# LEDMatrix.net
KiCad netlist of a schematic drawn in EAGLE
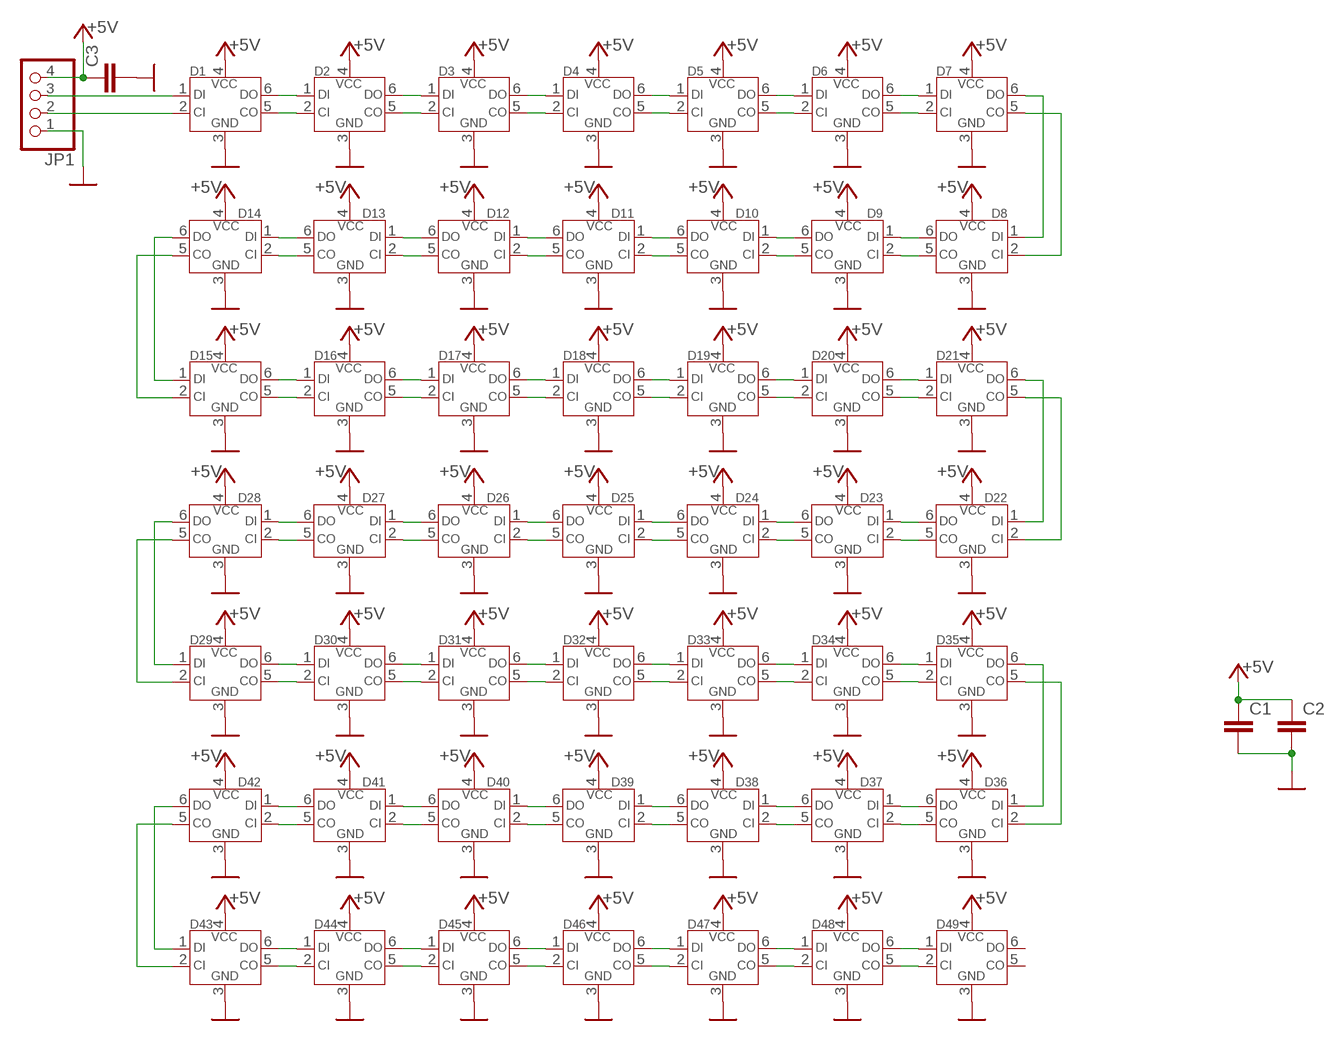
[diagram p0: schematic, sheet 1]

(export (version "E")
  (design (tool "Eeschema 10.0.6"))
  (components
    (comp (ref "C1")
      (value "C-EUC0805")
      (footprint "eagle-import:C0805")
      (libsource (lib "eagle-import") (part "C-EUC0805"))
    )
    (comp (ref "C2")
      (value "C-EUC0805")
      (footprint "eagle-import:C0805")
      (libsource (lib "eagle-import") (part "C-EUC0805"))
    )
    (comp (ref "C3")
      (value "C-EUC0805")
      (footprint "eagle-import:C0805")
      (libsource (lib "eagle-import") (part "C-EUC0805"))
    )
    (comp (ref "D1")
      (value "QBLP679E-RGB")
      (footprint "eagle-import:LED_QBLP679E-RGB")
      (fields (field (name "MF") "QT Brightek"))
      (libsource (lib "eagle-import") (part "QBLP679E-RGB"))
    )
    (comp (ref "D2")
      (value "QBLP679E-RGB")
      (footprint "eagle-import:LED_QBLP679E-RGB")
      (fields (field (name "MF") "QT Brightek"))
      (libsource (lib "eagle-import") (part "QBLP679E-RGB"))
    )
    (comp (ref "D3")
      (value "QBLP679E-RGB")
      (footprint "eagle-import:LED_QBLP679E-RGB")
      (fields (field (name "MF") "QT Brightek"))
      (libsource (lib "eagle-import") (part "QBLP679E-RGB"))
    )
    (comp (ref "D4")
      (value "QBLP679E-RGB")
      (footprint "eagle-import:LED_QBLP679E-RGB")
      (fields (field (name "MF") "QT Brightek"))
      (libsource (lib "eagle-import") (part "QBLP679E-RGB"))
    )
    (comp (ref "D5")
      (value "QBLP679E-RGB")
      (footprint "eagle-import:LED_QBLP679E-RGB")
      (fields (field (name "MF") "QT Brightek"))
      (libsource (lib "eagle-import") (part "QBLP679E-RGB"))
    )
    (comp (ref "D6")
      (value "QBLP679E-RGB")
      (footprint "eagle-import:LED_QBLP679E-RGB")
      (fields (field (name "MF") "QT Brightek"))
      (libsource (lib "eagle-import") (part "QBLP679E-RGB"))
    )
    (comp (ref "D7")
      (value "QBLP679E-RGB")
      (footprint "eagle-import:LED_QBLP679E-RGB")
      (fields (field (name "MF") "QT Brightek"))
      (libsource (lib "eagle-import") (part "QBLP679E-RGB"))
    )
    (comp (ref "D8")
      (value "QBLP679E-RGB")
      (footprint "eagle-import:LED_QBLP679E-RGB")
      (fields (field (name "MF") "QT Brightek"))
      (libsource (lib "eagle-import") (part "QBLP679E-RGB"))
    )
    (comp (ref "D9")
      (value "QBLP679E-RGB")
      (footprint "eagle-import:LED_QBLP679E-RGB")
      (fields (field (name "MF") "QT Brightek"))
      (libsource (lib "eagle-import") (part "QBLP679E-RGB"))
    )
    (comp (ref "D10")
      (value "QBLP679E-RGB")
      (footprint "eagle-import:LED_QBLP679E-RGB")
      (fields (field (name "MF") "QT Brightek"))
      (libsource (lib "eagle-import") (part "QBLP679E-RGB"))
    )
    (comp (ref "D11")
      (value "QBLP679E-RGB")
      (footprint "eagle-import:LED_QBLP679E-RGB")
      (fields (field (name "MF") "QT Brightek"))
      (libsource (lib "eagle-import") (part "QBLP679E-RGB"))
    )
    (comp (ref "D12")
      (value "QBLP679E-RGB")
      (footprint "eagle-import:LED_QBLP679E-RGB")
      (fields (field (name "MF") "QT Brightek"))
      (libsource (lib "eagle-import") (part "QBLP679E-RGB"))
    )
    (comp (ref "D13")
      (value "QBLP679E-RGB")
      (footprint "eagle-import:LED_QBLP679E-RGB")
      (fields (field (name "MF") "QT Brightek"))
      (libsource (lib "eagle-import") (part "QBLP679E-RGB"))
    )
    (comp (ref "D14")
      (value "QBLP679E-RGB")
      (footprint "eagle-import:LED_QBLP679E-RGB")
      (fields (field (name "MF") "QT Brightek"))
      (libsource (lib "eagle-import") (part "QBLP679E-RGB"))
    )
    (comp (ref "D15")
      (value "QBLP679E-RGB")
      (footprint "eagle-import:LED_QBLP679E-RGB")
      (fields (field (name "MF") "QT Brightek"))
      (libsource (lib "eagle-import") (part "QBLP679E-RGB"))
    )
    (comp (ref "D16")
      (value "QBLP679E-RGB")
      (footprint "eagle-import:LED_QBLP679E-RGB")
      (fields (field (name "MF") "QT Brightek"))
      (libsource (lib "eagle-import") (part "QBLP679E-RGB"))
    )
    (comp (ref "D17")
      (value "QBLP679E-RGB")
      (footprint "eagle-import:LED_QBLP679E-RGB")
      (fields (field (name "MF") "QT Brightek"))
      (libsource (lib "eagle-import") (part "QBLP679E-RGB"))
    )
    (comp (ref "D18")
      (value "QBLP679E-RGB")
      (footprint "eagle-import:LED_QBLP679E-RGB")
      (fields (field (name "MF") "QT Brightek"))
      (libsource (lib "eagle-import") (part "QBLP679E-RGB"))
    )
    (comp (ref "D19")
      (value "QBLP679E-RGB")
      (footprint "eagle-import:LED_QBLP679E-RGB")
      (fields (field (name "MF") "QT Brightek"))
      (libsource (lib "eagle-import") (part "QBLP679E-RGB"))
    )
    (comp (ref "D20")
      (value "QBLP679E-RGB")
      (footprint "eagle-import:LED_QBLP679E-RGB")
      (fields (field (name "MF") "QT Brightek"))
      (libsource (lib "eagle-import") (part "QBLP679E-RGB"))
    )
    (comp (ref "D21")
      (value "QBLP679E-RGB")
      (footprint "eagle-import:LED_QBLP679E-RGB")
      (fields (field (name "MF") "QT Brightek"))
      (libsource (lib "eagle-import") (part "QBLP679E-RGB"))
    )
    (comp (ref "D22")
      (value "QBLP679E-RGB")
      (footprint "eagle-import:LED_QBLP679E-RGB")
      (fields (field (name "MF") "QT Brightek"))
      (libsource (lib "eagle-import") (part "QBLP679E-RGB"))
    )
    (comp (ref "D23")
      (value "QBLP679E-RGB")
      (footprint "eagle-import:LED_QBLP679E-RGB")
      (fields (field (name "MF") "QT Brightek"))
      (libsource (lib "eagle-import") (part "QBLP679E-RGB"))
    )
    (comp (ref "D24")
      (value "QBLP679E-RGB")
      (footprint "eagle-import:LED_QBLP679E-RGB")
      (fields (field (name "MF") "QT Brightek"))
      (libsource (lib "eagle-import") (part "QBLP679E-RGB"))
    )
    (comp (ref "D25")
      (value "QBLP679E-RGB")
      (footprint "eagle-import:LED_QBLP679E-RGB")
      (fields (field (name "MF") "QT Brightek"))
      (libsource (lib "eagle-import") (part "QBLP679E-RGB"))
    )
    (comp (ref "D26")
      (value "QBLP679E-RGB")
      (footprint "eagle-import:LED_QBLP679E-RGB")
      (fields (field (name "MF") "QT Brightek"))
      (libsource (lib "eagle-import") (part "QBLP679E-RGB"))
    )
    (comp (ref "D27")
      (value "QBLP679E-RGB")
      (footprint "eagle-import:LED_QBLP679E-RGB")
      (fields (field (name "MF") "QT Brightek"))
      (libsource (lib "eagle-import") (part "QBLP679E-RGB"))
    )
    (comp (ref "D28")
      (value "QBLP679E-RGB")
      (footprint "eagle-import:LED_QBLP679E-RGB")
      (fields (field (name "MF") "QT Brightek"))
      (libsource (lib "eagle-import") (part "QBLP679E-RGB"))
    )
    (comp (ref "D29")
      (value "QBLP679E-RGB")
      (footprint "eagle-import:LED_QBLP679E-RGB")
      (fields (field (name "MF") "QT Brightek"))
      (libsource (lib "eagle-import") (part "QBLP679E-RGB"))
    )
    (comp (ref "D30")
      (value "QBLP679E-RGB")
      (footprint "eagle-import:LED_QBLP679E-RGB")
      (fields (field (name "MF") "QT Brightek"))
      (libsource (lib "eagle-import") (part "QBLP679E-RGB"))
    )
    (comp (ref "D31")
      (value "QBLP679E-RGB")
      (footprint "eagle-import:LED_QBLP679E-RGB")
      (fields (field (name "MF") "QT Brightek"))
      (libsource (lib "eagle-import") (part "QBLP679E-RGB"))
    )
    (comp (ref "D32")
      (value "QBLP679E-RGB")
      (footprint "eagle-import:LED_QBLP679E-RGB")
      (fields (field (name "MF") "QT Brightek"))
      (libsource (lib "eagle-import") (part "QBLP679E-RGB"))
    )
    (comp (ref "D33")
      (value "QBLP679E-RGB")
      (footprint "eagle-import:LED_QBLP679E-RGB")
      (fields (field (name "MF") "QT Brightek"))
      (libsource (lib "eagle-import") (part "QBLP679E-RGB"))
    )
    (comp (ref "D34")
      (value "QBLP679E-RGB")
      (footprint "eagle-import:LED_QBLP679E-RGB")
      (fields (field (name "MF") "QT Brightek"))
      (libsource (lib "eagle-import") (part "QBLP679E-RGB"))
    )
    (comp (ref "D35")
      (value "QBLP679E-RGB")
      (footprint "eagle-import:LED_QBLP679E-RGB")
      (fields (field (name "MF") "QT Brightek"))
      (libsource (lib "eagle-import") (part "QBLP679E-RGB"))
    )
    (comp (ref "D36")
      (value "QBLP679E-RGB")
      (footprint "eagle-import:LED_QBLP679E-RGB")
      (fields (field (name "MF") "QT Brightek"))
      (libsource (lib "eagle-import") (part "QBLP679E-RGB"))
    )
    (comp (ref "D37")
      (value "QBLP679E-RGB")
      (footprint "eagle-import:LED_QBLP679E-RGB")
      (fields (field (name "MF") "QT Brightek"))
      (libsource (lib "eagle-import") (part "QBLP679E-RGB"))
    )
    (comp (ref "D38")
      (value "QBLP679E-RGB")
      (footprint "eagle-import:LED_QBLP679E-RGB")
      (fields (field (name "MF") "QT Brightek"))
      (libsource (lib "eagle-import") (part "QBLP679E-RGB"))
    )
    (comp (ref "D39")
      (value "QBLP679E-RGB")
      (footprint "eagle-import:LED_QBLP679E-RGB")
      (fields (field (name "MF") "QT Brightek"))
      (libsource (lib "eagle-import") (part "QBLP679E-RGB"))
    )
    (comp (ref "D40")
      (value "QBLP679E-RGB")
      (footprint "eagle-import:LED_QBLP679E-RGB")
      (fields (field (name "MF") "QT Brightek"))
      (libsource (lib "eagle-import") (part "QBLP679E-RGB"))
    )
    (comp (ref "D41")
      (value "QBLP679E-RGB")
      (footprint "eagle-import:LED_QBLP679E-RGB")
      (fields (field (name "MF") "QT Brightek"))
      (libsource (lib "eagle-import") (part "QBLP679E-RGB"))
    )
    (comp (ref "D42")
      (value "QBLP679E-RGB")
      (footprint "eagle-import:LED_QBLP679E-RGB")
      (fields (field (name "MF") "QT Brightek"))
      (libsource (lib "eagle-import") (part "QBLP679E-RGB"))
    )
    (comp (ref "D43")
      (value "QBLP679E-RGB")
      (footprint "eagle-import:LED_QBLP679E-RGB")
      (fields (field (name "MF") "QT Brightek"))
      (libsource (lib "eagle-import") (part "QBLP679E-RGB"))
    )
    (comp (ref "D44")
      (value "QBLP679E-RGB")
      (footprint "eagle-import:LED_QBLP679E-RGB")
      (fields (field (name "MF") "QT Brightek"))
      (libsource (lib "eagle-import") (part "QBLP679E-RGB"))
    )
    (comp (ref "D45")
      (value "QBLP679E-RGB")
      (footprint "eagle-import:LED_QBLP679E-RGB")
      (fields (field (name "MF") "QT Brightek"))
      (libsource (lib "eagle-import") (part "QBLP679E-RGB"))
    )
    (comp (ref "D46")
      (value "QBLP679E-RGB")
      (footprint "eagle-import:LED_QBLP679E-RGB")
      (fields (field (name "MF") "QT Brightek"))
      (libsource (lib "eagle-import") (part "QBLP679E-RGB"))
    )
    (comp (ref "D47")
      (value "QBLP679E-RGB")
      (footprint "eagle-import:LED_QBLP679E-RGB")
      (fields (field (name "MF") "QT Brightek"))
      (libsource (lib "eagle-import") (part "QBLP679E-RGB"))
    )
    (comp (ref "D48")
      (value "QBLP679E-RGB")
      (footprint "eagle-import:LED_QBLP679E-RGB")
      (fields (field (name "MF") "QT Brightek"))
      (libsource (lib "eagle-import") (part "QBLP679E-RGB"))
    )
    (comp (ref "D49")
      (value "QBLP679E-RGB")
      (footprint "eagle-import:LED_QBLP679E-RGB")
      (fields (field (name "MF") "QT Brightek"))
      (libsource (lib "eagle-import") (part "QBLP679E-RGB"))
    )
    (comp (ref "JP1")
      (value "PINHD-1X4")
      (footprint "eagle-import:1X04")
      (libsource (lib "eagle-import") (part "PINHD-1X4"))
    )
  )
  (nets
    (net (code "1") (name "+5V") (class "Default")
      (node (ref "C1") (pin "1") (pinfunction "1_1") (pintype "passive"))
      (node (ref "C2") (pin "1") (pinfunction "1_1") (pintype "passive"))
      (node (ref "C3") (pin "1") (pinfunction "1_1") (pintype "passive"))
      (node (ref "D1") (pin "4") (pinfunction "VCC_4") (pintype "bidirectional"))
      (node (ref "D10") (pin "4") (pinfunction "VCC_4") (pintype "bidirectional"))
      (node (ref "D11") (pin "4") (pinfunction "VCC_4") (pintype "bidirectional"))
      (node (ref "D12") (pin "4") (pinfunction "VCC_4") (pintype "bidirectional"))
      (node (ref "D13") (pin "4") (pinfunction "VCC_4") (pintype "bidirectional"))
      (node (ref "D14") (pin "4") (pinfunction "VCC_4") (pintype "bidirectional"))
      (node (ref "D15") (pin "4") (pinfunction "VCC_4") (pintype "bidirectional"))
      (node (ref "D16") (pin "4") (pinfunction "VCC_4") (pintype "bidirectional"))
      (node (ref "D17") (pin "4") (pinfunction "VCC_4") (pintype "bidirectional"))
      (node (ref "D18") (pin "4") (pinfunction "VCC_4") (pintype "bidirectional"))
      (node (ref "D19") (pin "4") (pinfunction "VCC_4") (pintype "bidirectional"))
      (node (ref "D2") (pin "4") (pinfunction "VCC_4") (pintype "bidirectional"))
      (node (ref "D20") (pin "4") (pinfunction "VCC_4") (pintype "bidirectional"))
      (node (ref "D21") (pin "4") (pinfunction "VCC_4") (pintype "bidirectional"))
      (node (ref "D22") (pin "4") (pinfunction "VCC_4") (pintype "bidirectional"))
      (node (ref "D23") (pin "4") (pinfunction "VCC_4") (pintype "bidirectional"))
      (node (ref "D24") (pin "4") (pinfunction "VCC_4") (pintype "bidirectional"))
      (node (ref "D25") (pin "4") (pinfunction "VCC_4") (pintype "bidirectional"))
      (node (ref "D26") (pin "4") (pinfunction "VCC_4") (pintype "bidirectional"))
      (node (ref "D27") (pin "4") (pinfunction "VCC_4") (pintype "bidirectional"))
      (node (ref "D28") (pin "4") (pinfunction "VCC_4") (pintype "bidirectional"))
      (node (ref "D29") (pin "4") (pinfunction "VCC_4") (pintype "bidirectional"))
      (node (ref "D3") (pin "4") (pinfunction "VCC_4") (pintype "bidirectional"))
      (node (ref "D30") (pin "4") (pinfunction "VCC_4") (pintype "bidirectional"))
      (node (ref "D31") (pin "4") (pinfunction "VCC_4") (pintype "bidirectional"))
      (node (ref "D32") (pin "4") (pinfunction "VCC_4") (pintype "bidirectional"))
      (node (ref "D33") (pin "4") (pinfunction "VCC_4") (pintype "bidirectional"))
      (node (ref "D34") (pin "4") (pinfunction "VCC_4") (pintype "bidirectional"))
      (node (ref "D35") (pin "4") (pinfunction "VCC_4") (pintype "bidirectional"))
      (node (ref "D36") (pin "4") (pinfunction "VCC_4") (pintype "bidirectional"))
      (node (ref "D37") (pin "4") (pinfunction "VCC_4") (pintype "bidirectional"))
      (node (ref "D38") (pin "4") (pinfunction "VCC_4") (pintype "bidirectional"))
      (node (ref "D39") (pin "4") (pinfunction "VCC_4") (pintype "bidirectional"))
      (node (ref "D4") (pin "4") (pinfunction "VCC_4") (pintype "bidirectional"))
      (node (ref "D40") (pin "4") (pinfunction "VCC_4") (pintype "bidirectional"))
      (node (ref "D41") (pin "4") (pinfunction "VCC_4") (pintype "bidirectional"))
      (node (ref "D42") (pin "4") (pinfunction "VCC_4") (pintype "bidirectional"))
      (node (ref "D43") (pin "4") (pinfunction "VCC_4") (pintype "bidirectional"))
      (node (ref "D44") (pin "4") (pinfunction "VCC_4") (pintype "bidirectional"))
      (node (ref "D45") (pin "4") (pinfunction "VCC_4") (pintype "bidirectional"))
      (node (ref "D46") (pin "4") (pinfunction "VCC_4") (pintype "bidirectional"))
      (node (ref "D47") (pin "4") (pinfunction "VCC_4") (pintype "bidirectional"))
      (node (ref "D48") (pin "4") (pinfunction "VCC_4") (pintype "bidirectional"))
      (node (ref "D49") (pin "4") (pinfunction "VCC_4") (pintype "bidirectional"))
      (node (ref "D5") (pin "4") (pinfunction "VCC_4") (pintype "bidirectional"))
      (node (ref "D6") (pin "4") (pinfunction "VCC_4") (pintype "bidirectional"))
      (node (ref "D7") (pin "4") (pinfunction "VCC_4") (pintype "bidirectional"))
      (node (ref "D8") (pin "4") (pinfunction "VCC_4") (pintype "bidirectional"))
      (node (ref "D9") (pin "4") (pinfunction "VCC_4") (pintype "bidirectional"))
      (node (ref "JP1") (pin "4") (pinfunction "4_4") (pintype "passive"))
    )
    (net (code "2") (name "GND") (class "Default")
      (node (ref "C1") (pin "2") (pinfunction "2_2") (pintype "passive"))
      (node (ref "C2") (pin "2") (pinfunction "2_2") (pintype "passive"))
      (node (ref "C3") (pin "2") (pinfunction "2_2") (pintype "passive"))
      (node (ref "D1") (pin "3") (pinfunction "GND_3") (pintype "bidirectional"))
      (node (ref "D10") (pin "3") (pinfunction "GND_3") (pintype "bidirectional"))
      (node (ref "D11") (pin "3") (pinfunction "GND_3") (pintype "bidirectional"))
      (node (ref "D12") (pin "3") (pinfunction "GND_3") (pintype "bidirectional"))
      (node (ref "D13") (pin "3") (pinfunction "GND_3") (pintype "bidirectional"))
      (node (ref "D14") (pin "3") (pinfunction "GND_3") (pintype "bidirectional"))
      (node (ref "D15") (pin "3") (pinfunction "GND_3") (pintype "bidirectional"))
      (node (ref "D16") (pin "3") (pinfunction "GND_3") (pintype "bidirectional"))
      (node (ref "D17") (pin "3") (pinfunction "GND_3") (pintype "bidirectional"))
      (node (ref "D18") (pin "3") (pinfunction "GND_3") (pintype "bidirectional"))
      (node (ref "D19") (pin "3") (pinfunction "GND_3") (pintype "bidirectional"))
      (node (ref "D2") (pin "3") (pinfunction "GND_3") (pintype "bidirectional"))
      (node (ref "D20") (pin "3") (pinfunction "GND_3") (pintype "bidirectional"))
      (node (ref "D21") (pin "3") (pinfunction "GND_3") (pintype "bidirectional"))
      (node (ref "D22") (pin "3") (pinfunction "GND_3") (pintype "bidirectional"))
      (node (ref "D23") (pin "3") (pinfunction "GND_3") (pintype "bidirectional"))
      (node (ref "D24") (pin "3") (pinfunction "GND_3") (pintype "bidirectional"))
      (node (ref "D25") (pin "3") (pinfunction "GND_3") (pintype "bidirectional"))
      (node (ref "D26") (pin "3") (pinfunction "GND_3") (pintype "bidirectional"))
      (node (ref "D27") (pin "3") (pinfunction "GND_3") (pintype "bidirectional"))
      (node (ref "D28") (pin "3") (pinfunction "GND_3") (pintype "bidirectional"))
      (node (ref "D29") (pin "3") (pinfunction "GND_3") (pintype "bidirectional"))
      (node (ref "D3") (pin "3") (pinfunction "GND_3") (pintype "bidirectional"))
      (node (ref "D30") (pin "3") (pinfunction "GND_3") (pintype "bidirectional"))
      (node (ref "D31") (pin "3") (pinfunction "GND_3") (pintype "bidirectional"))
      (node (ref "D32") (pin "3") (pinfunction "GND_3") (pintype "bidirectional"))
      (node (ref "D33") (pin "3") (pinfunction "GND_3") (pintype "bidirectional"))
      (node (ref "D34") (pin "3") (pinfunction "GND_3") (pintype "bidirectional"))
      (node (ref "D35") (pin "3") (pinfunction "GND_3") (pintype "bidirectional"))
      (node (ref "D36") (pin "3") (pinfunction "GND_3") (pintype "bidirectional"))
      (node (ref "D37") (pin "3") (pinfunction "GND_3") (pintype "bidirectional"))
      (node (ref "D38") (pin "3") (pinfunction "GND_3") (pintype "bidirectional"))
      (node (ref "D39") (pin "3") (pinfunction "GND_3") (pintype "bidirectional"))
      (node (ref "D4") (pin "3") (pinfunction "GND_3") (pintype "bidirectional"))
      (node (ref "D40") (pin "3") (pinfunction "GND_3") (pintype "bidirectional"))
      (node (ref "D41") (pin "3") (pinfunction "GND_3") (pintype "bidirectional"))
      (node (ref "D42") (pin "3") (pinfunction "GND_3") (pintype "bidirectional"))
      (node (ref "D43") (pin "3") (pinfunction "GND_3") (pintype "bidirectional"))
      (node (ref "D44") (pin "3") (pinfunction "GND_3") (pintype "bidirectional"))
      (node (ref "D45") (pin "3") (pinfunction "GND_3") (pintype "bidirectional"))
      (node (ref "D46") (pin "3") (pinfunction "GND_3") (pintype "bidirectional"))
      (node (ref "D47") (pin "3") (pinfunction "GND_3") (pintype "bidirectional"))
      (node (ref "D48") (pin "3") (pinfunction "GND_3") (pintype "bidirectional"))
      (node (ref "D49") (pin "3") (pinfunction "GND_3") (pintype "bidirectional"))
      (node (ref "D5") (pin "3") (pinfunction "GND_3") (pintype "bidirectional"))
      (node (ref "D6") (pin "3") (pinfunction "GND_3") (pintype "bidirectional"))
      (node (ref "D7") (pin "3") (pinfunction "GND_3") (pintype "bidirectional"))
      (node (ref "D8") (pin "3") (pinfunction "GND_3") (pintype "bidirectional"))
      (node (ref "D9") (pin "3") (pinfunction "GND_3") (pintype "bidirectional"))
      (node (ref "JP1") (pin "1") (pinfunction "1_1") (pintype "passive"))
    )
    (net (code "3") (name "Net-(D1-CI)") (class "Default")
      (node (ref "D1") (pin "2") (pinfunction "CI_2") (pintype "bidirectional"))
      (node (ref "JP1") (pin "2") (pinfunction "2_2") (pintype "passive"))
    )
    (net (code "4") (name "Net-(D1-CO)") (class "Default")
      (node (ref "D1") (pin "5") (pinfunction "CO_5") (pintype "bidirectional"))
      (node (ref "D2") (pin "2") (pinfunction "CI_2") (pintype "bidirectional"))
    )
    (net (code "5") (name "Net-(D1-DI)") (class "Default")
      (node (ref "D1") (pin "1") (pinfunction "DI_1") (pintype "bidirectional"))
      (node (ref "JP1") (pin "3") (pinfunction "3_3") (pintype "passive"))
    )
    (net (code "6") (name "Net-(D1-DO)") (class "Default")
      (node (ref "D1") (pin "6") (pinfunction "DO_6") (pintype "bidirectional"))
      (node (ref "D2") (pin "1") (pinfunction "DI_1") (pintype "bidirectional"))
    )
    (net (code "7") (name "Net-(D2-CO)") (class "Default")
      (node (ref "D2") (pin "5") (pinfunction "CO_5") (pintype "bidirectional"))
      (node (ref "D3") (pin "2") (pinfunction "CI_2") (pintype "bidirectional"))
    )
    (net (code "8") (name "Net-(D2-DO)") (class "Default")
      (node (ref "D2") (pin "6") (pinfunction "DO_6") (pintype "bidirectional"))
      (node (ref "D3") (pin "1") (pinfunction "DI_1") (pintype "bidirectional"))
    )
    (net (code "9") (name "Net-(D3-CO)") (class "Default")
      (node (ref "D3") (pin "5") (pinfunction "CO_5") (pintype "bidirectional"))
      (node (ref "D4") (pin "2") (pinfunction "CI_2") (pintype "bidirectional"))
    )
    (net (code "10") (name "Net-(D3-DO)") (class "Default")
      (node (ref "D3") (pin "6") (pinfunction "DO_6") (pintype "bidirectional"))
      (node (ref "D4") (pin "1") (pinfunction "DI_1") (pintype "bidirectional"))
    )
    (net (code "11") (name "Net-(D4-CO)") (class "Default")
      (node (ref "D4") (pin "5") (pinfunction "CO_5") (pintype "bidirectional"))
      (node (ref "D5") (pin "2") (pinfunction "CI_2") (pintype "bidirectional"))
    )
    (net (code "12") (name "Net-(D4-DO)") (class "Default")
      (node (ref "D4") (pin "6") (pinfunction "DO_6") (pintype "bidirectional"))
      (node (ref "D5") (pin "1") (pinfunction "DI_1") (pintype "bidirectional"))
    )
    (net (code "13") (name "Net-(D5-CO)") (class "Default")
      (node (ref "D5") (pin "5") (pinfunction "CO_5") (pintype "bidirectional"))
      (node (ref "D6") (pin "2") (pinfunction "CI_2") (pintype "bidirectional"))
    )
    (net (code "14") (name "Net-(D5-DO)") (class "Default")
      (node (ref "D5") (pin "6") (pinfunction "DO_6") (pintype "bidirectional"))
      (node (ref "D6") (pin "1") (pinfunction "DI_1") (pintype "bidirectional"))
    )
    (net (code "15") (name "Net-(D6-CO)") (class "Default")
      (node (ref "D6") (pin "5") (pinfunction "CO_5") (pintype "bidirectional"))
      (node (ref "D7") (pin "2") (pinfunction "CI_2") (pintype "bidirectional"))
    )
    (net (code "16") (name "Net-(D6-DO)") (class "Default")
      (node (ref "D6") (pin "6") (pinfunction "DO_6") (pintype "bidirectional"))
      (node (ref "D7") (pin "1") (pinfunction "DI_1") (pintype "bidirectional"))
    )
    (net (code "17") (name "Net-(D7-CO)") (class "Default")
      (node (ref "D7") (pin "5") (pinfunction "CO_5") (pintype "bidirectional"))
      (node (ref "D8") (pin "2") (pinfunction "CI_2") (pintype "bidirectional"))
    )
    (net (code "18") (name "Net-(D7-DO)") (class "Default")
      (node (ref "D7") (pin "6") (pinfunction "DO_6") (pintype "bidirectional"))
      (node (ref "D8") (pin "1") (pinfunction "DI_1") (pintype "bidirectional"))
    )
    (net (code "19") (name "Net-(D8-CO)") (class "Default")
      (node (ref "D8") (pin "5") (pinfunction "CO_5") (pintype "bidirectional"))
      (node (ref "D9") (pin "2") (pinfunction "CI_2") (pintype "bidirectional"))
    )
    (net (code "20") (name "Net-(D8-DO)") (class "Default")
      (node (ref "D8") (pin "6") (pinfunction "DO_6") (pintype "bidirectional"))
      (node (ref "D9") (pin "1") (pinfunction "DI_1") (pintype "bidirectional"))
    )
    (net (code "21") (name "Net-(D10-CI)") (class "Default")
      (node (ref "D10") (pin "2") (pinfunction "CI_2") (pintype "bidirectional"))
      (node (ref "D9") (pin "5") (pinfunction "CO_5") (pintype "bidirectional"))
    )
    (net (code "22") (name "Net-(D10-CO)") (class "Default")
      (node (ref "D10") (pin "5") (pinfunction "CO_5") (pintype "bidirectional"))
      (node (ref "D11") (pin "2") (pinfunction "CI_2") (pintype "bidirectional"))
    )
    (net (code "23") (name "Net-(D10-DI)") (class "Default")
      (node (ref "D10") (pin "1") (pinfunction "DI_1") (pintype "bidirectional"))
      (node (ref "D9") (pin "6") (pinfunction "DO_6") (pintype "bidirectional"))
    )
    (net (code "24") (name "Net-(D10-DO)") (class "Default")
      (node (ref "D10") (pin "6") (pinfunction "DO_6") (pintype "bidirectional"))
      (node (ref "D11") (pin "1") (pinfunction "DI_1") (pintype "bidirectional"))
    )
    (net (code "25") (name "Net-(D11-CO)") (class "Default")
      (node (ref "D11") (pin "5") (pinfunction "CO_5") (pintype "bidirectional"))
      (node (ref "D12") (pin "2") (pinfunction "CI_2") (pintype "bidirectional"))
    )
    (net (code "26") (name "Net-(D11-DO)") (class "Default")
      (node (ref "D11") (pin "6") (pinfunction "DO_6") (pintype "bidirectional"))
      (node (ref "D12") (pin "1") (pinfunction "DI_1") (pintype "bidirectional"))
    )
    (net (code "27") (name "Net-(D12-CO)") (class "Default")
      (node (ref "D12") (pin "5") (pinfunction "CO_5") (pintype "bidirectional"))
      (node (ref "D13") (pin "2") (pinfunction "CI_2") (pintype "bidirectional"))
    )
    (net (code "28") (name "Net-(D12-DO)") (class "Default")
      (node (ref "D12") (pin "6") (pinfunction "DO_6") (pintype "bidirectional"))
      (node (ref "D13") (pin "1") (pinfunction "DI_1") (pintype "bidirectional"))
    )
    (net (code "29") (name "Net-(D13-CO)") (class "Default")
      (node (ref "D13") (pin "5") (pinfunction "CO_5") (pintype "bidirectional"))
      (node (ref "D14") (pin "2") (pinfunction "CI_2") (pintype "bidirectional"))
    )
    (net (code "30") (name "Net-(D13-DO)") (class "Default")
      (node (ref "D13") (pin "6") (pinfunction "DO_6") (pintype "bidirectional"))
      (node (ref "D14") (pin "1") (pinfunction "DI_1") (pintype "bidirectional"))
    )
    (net (code "31") (name "Net-(D14-CO)") (class "Default")
      (node (ref "D14") (pin "5") (pinfunction "CO_5") (pintype "bidirectional"))
      (node (ref "D15") (pin "2") (pinfunction "CI_2") (pintype "bidirectional"))
    )
    (net (code "32") (name "Net-(D14-DO)") (class "Default")
      (node (ref "D14") (pin "6") (pinfunction "DO_6") (pintype "bidirectional"))
      (node (ref "D15") (pin "1") (pinfunction "DI_1") (pintype "bidirectional"))
    )
    (net (code "33") (name "Net-(D15-CO)") (class "Default")
      (node (ref "D15") (pin "5") (pinfunction "CO_5") (pintype "bidirectional"))
      (node (ref "D16") (pin "2") (pinfunction "CI_2") (pintype "bidirectional"))
    )
    (net (code "34") (name "Net-(D15-DO)") (class "Default")
      (node (ref "D15") (pin "6") (pinfunction "DO_6") (pintype "bidirectional"))
      (node (ref "D16") (pin "1") (pinfunction "DI_1") (pintype "bidirectional"))
    )
    (net (code "35") (name "Net-(D16-CO)") (class "Default")
      (node (ref "D16") (pin "5") (pinfunction "CO_5") (pintype "bidirectional"))
      (node (ref "D17") (pin "2") (pinfunction "CI_2") (pintype "bidirectional"))
    )
    (net (code "36") (name "Net-(D16-DO)") (class "Default")
      (node (ref "D16") (pin "6") (pinfunction "DO_6") (pintype "bidirectional"))
      (node (ref "D17") (pin "1") (pinfunction "DI_1") (pintype "bidirectional"))
    )
    (net (code "37") (name "Net-(D17-CO)") (class "Default")
      (node (ref "D17") (pin "5") (pinfunction "CO_5") (pintype "bidirectional"))
      (node (ref "D18") (pin "2") (pinfunction "CI_2") (pintype "bidirectional"))
    )
    (net (code "38") (name "Net-(D17-DO)") (class "Default")
      (node (ref "D17") (pin "6") (pinfunction "DO_6") (pintype "bidirectional"))
      (node (ref "D18") (pin "1") (pinfunction "DI_1") (pintype "bidirectional"))
    )
    (net (code "39") (name "Net-(D18-CO)") (class "Default")
      (node (ref "D18") (pin "5") (pinfunction "CO_5") (pintype "bidirectional"))
      (node (ref "D19") (pin "2") (pinfunction "CI_2") (pintype "bidirectional"))
    )
    (net (code "40") (name "Net-(D18-DO)") (class "Default")
      (node (ref "D18") (pin "6") (pinfunction "DO_6") (pintype "bidirectional"))
      (node (ref "D19") (pin "1") (pinfunction "DI_1") (pintype "bidirectional"))
    )
    (net (code "41") (name "Net-(D19-CO)") (class "Default")
      (node (ref "D19") (pin "5") (pinfunction "CO_5") (pintype "bidirectional"))
      (node (ref "D20") (pin "2") (pinfunction "CI_2") (pintype "bidirectional"))
    )
    (net (code "42") (name "Net-(D19-DO)") (class "Default")
      (node (ref "D19") (pin "6") (pinfunction "DO_6") (pintype "bidirectional"))
      (node (ref "D20") (pin "1") (pinfunction "DI_1") (pintype "bidirectional"))
    )
    (net (code "43") (name "Net-(D20-CO)") (class "Default")
      (node (ref "D20") (pin "5") (pinfunction "CO_5") (pintype "bidirectional"))
      (node (ref "D21") (pin "2") (pinfunction "CI_2") (pintype "bidirectional"))
    )
    (net (code "44") (name "Net-(D20-DO)") (class "Default")
      (node (ref "D20") (pin "6") (pinfunction "DO_6") (pintype "bidirectional"))
      (node (ref "D21") (pin "1") (pinfunction "DI_1") (pintype "bidirectional"))
    )
    (net (code "45") (name "Net-(D21-CO)") (class "Default")
      (node (ref "D21") (pin "5") (pinfunction "CO_5") (pintype "bidirectional"))
      (node (ref "D22") (pin "2") (pinfunction "CI_2") (pintype "bidirectional"))
    )
    (net (code "46") (name "Net-(D21-DO)") (class "Default")
      (node (ref "D21") (pin "6") (pinfunction "DO_6") (pintype "bidirectional"))
      (node (ref "D22") (pin "1") (pinfunction "DI_1") (pintype "bidirectional"))
    )
    (net (code "47") (name "Net-(D22-CO)") (class "Default")
      (node (ref "D22") (pin "5") (pinfunction "CO_5") (pintype "bidirectional"))
      (node (ref "D23") (pin "2") (pinfunction "CI_2") (pintype "bidirectional"))
    )
    (net (code "48") (name "Net-(D22-DO)") (class "Default")
      (node (ref "D22") (pin "6") (pinfunction "DO_6") (pintype "bidirectional"))
      (node (ref "D23") (pin "1") (pinfunction "DI_1") (pintype "bidirectional"))
    )
    (net (code "49") (name "Net-(D23-CO)") (class "Default")
      (node (ref "D23") (pin "5") (pinfunction "CO_5") (pintype "bidirectional"))
      (node (ref "D24") (pin "2") (pinfunction "CI_2") (pintype "bidirectional"))
    )
    (net (code "50") (name "Net-(D23-DO)") (class "Default")
      (node (ref "D23") (pin "6") (pinfunction "DO_6") (pintype "bidirectional"))
      (node (ref "D24") (pin "1") (pinfunction "DI_1") (pintype "bidirectional"))
    )
    (net (code "51") (name "Net-(D24-CO)") (class "Default")
      (node (ref "D24") (pin "5") (pinfunction "CO_5") (pintype "bidirectional"))
      (node (ref "D25") (pin "2") (pinfunction "CI_2") (pintype "bidirectional"))
    )
    (net (code "52") (name "Net-(D24-DO)") (class "Default")
      (node (ref "D24") (pin "6") (pinfunction "DO_6") (pintype "bidirectional"))
      (node (ref "D25") (pin "1") (pinfunction "DI_1") (pintype "bidirectional"))
    )
    (net (code "53") (name "Net-(D25-CO)") (class "Default")
      (node (ref "D25") (pin "5") (pinfunction "CO_5") (pintype "bidirectional"))
      (node (ref "D26") (pin "2") (pinfunction "CI_2") (pintype "bidirectional"))
    )
    (net (code "54") (name "Net-(D25-DO)") (class "Default")
      (node (ref "D25") (pin "6") (pinfunction "DO_6") (pintype "bidirectional"))
      (node (ref "D26") (pin "1") (pinfunction "DI_1") (pintype "bidirectional"))
    )
    (net (code "55") (name "Net-(D26-CO)") (class "Default")
      (node (ref "D26") (pin "5") (pinfunction "CO_5") (pintype "bidirectional"))
      (node (ref "D27") (pin "2") (pinfunction "CI_2") (pintype "bidirectional"))
    )
    (net (code "56") (name "Net-(D26-DO)") (class "Default")
      (node (ref "D26") (pin "6") (pinfunction "DO_6") (pintype "bidirectional"))
      (node (ref "D27") (pin "1") (pinfunction "DI_1") (pintype "bidirectional"))
    )
    (net (code "57") (name "Net-(D27-CO)") (class "Default")
      (node (ref "D27") (pin "5") (pinfunction "CO_5") (pintype "bidirectional"))
      (node (ref "D28") (pin "2") (pinfunction "CI_2") (pintype "bidirectional"))
    )
    (net (code "58") (name "Net-(D27-DO)") (class "Default")
      (node (ref "D27") (pin "6") (pinfunction "DO_6") (pintype "bidirectional"))
      (node (ref "D28") (pin "1") (pinfunction "DI_1") (pintype "bidirectional"))
    )
    (net (code "59") (name "Net-(D28-CO)") (class "Default")
      (node (ref "D28") (pin "5") (pinfunction "CO_5") (pintype "bidirectional"))
      (node (ref "D29") (pin "2") (pinfunction "CI_2") (pintype "bidirectional"))
    )
    (net (code "60") (name "Net-(D28-DO)") (class "Default")
      (node (ref "D28") (pin "6") (pinfunction "DO_6") (pintype "bidirectional"))
      (node (ref "D29") (pin "1") (pinfunction "DI_1") (pintype "bidirectional"))
    )
    (net (code "61") (name "Net-(D29-CO)") (class "Default")
      (node (ref "D29") (pin "5") (pinfunction "CO_5") (pintype "bidirectional"))
      (node (ref "D30") (pin "2") (pinfunction "CI_2") (pintype "bidirectional"))
    )
    (net (code "62") (name "Net-(D29-DO)") (class "Default")
      (node (ref "D29") (pin "6") (pinfunction "DO_6") (pintype "bidirectional"))
      (node (ref "D30") (pin "1") (pinfunction "DI_1") (pintype "bidirectional"))
    )
    (net (code "63") (name "Net-(D30-CO)") (class "Default")
      (node (ref "D30") (pin "5") (pinfunction "CO_5") (pintype "bidirectional"))
      (node (ref "D31") (pin "2") (pinfunction "CI_2") (pintype "bidirectional"))
    )
    (net (code "64") (name "Net-(D30-DO)") (class "Default")
      (node (ref "D30") (pin "6") (pinfunction "DO_6") (pintype "bidirectional"))
      (node (ref "D31") (pin "1") (pinfunction "DI_1") (pintype "bidirectional"))
    )
    (net (code "65") (name "Net-(D31-CO)") (class "Default")
      (node (ref "D31") (pin "5") (pinfunction "CO_5") (pintype "bidirectional"))
      (node (ref "D32") (pin "2") (pinfunction "CI_2") (pintype "bidirectional"))
    )
    (net (code "66") (name "Net-(D31-DO)") (class "Default")
      (node (ref "D31") (pin "6") (pinfunction "DO_6") (pintype "bidirectional"))
      (node (ref "D32") (pin "1") (pinfunction "DI_1") (pintype "bidirectional"))
    )
    (net (code "67") (name "Net-(D32-CO)") (class "Default")
      (node (ref "D32") (pin "5") (pinfunction "CO_5") (pintype "bidirectional"))
      (node (ref "D33") (pin "2") (pinfunction "CI_2") (pintype "bidirectional"))
    )
    (net (code "68") (name "Net-(D32-DO)") (class "Default")
      (node (ref "D32") (pin "6") (pinfunction "DO_6") (pintype "bidirectional"))
      (node (ref "D33") (pin "1") (pinfunction "DI_1") (pintype "bidirectional"))
    )
    (net (code "69") (name "Net-(D33-CO)") (class "Default")
      (node (ref "D33") (pin "5") (pinfunction "CO_5") (pintype "bidirectional"))
      (node (ref "D34") (pin "2") (pinfunction "CI_2") (pintype "bidirectional"))
    )
    (net (code "70") (name "Net-(D33-DO)") (class "Default")
      (node (ref "D33") (pin "6") (pinfunction "DO_6") (pintype "bidirectional"))
      (node (ref "D34") (pin "1") (pinfunction "DI_1") (pintype "bidirectional"))
    )
    (net (code "71") (name "Net-(D34-CO)") (class "Default")
      (node (ref "D34") (pin "5") (pinfunction "CO_5") (pintype "bidirectional"))
      (node (ref "D35") (pin "2") (pinfunction "CI_2") (pintype "bidirectional"))
    )
    (net (code "72") (name "Net-(D34-DO)") (class "Default")
      (node (ref "D34") (pin "6") (pinfunction "DO_6") (pintype "bidirectional"))
      (node (ref "D35") (pin "1") (pinfunction "DI_1") (pintype "bidirectional"))
    )
    (net (code "73") (name "Net-(D35-CO)") (class "Default")
      (node (ref "D35") (pin "5") (pinfunction "CO_5") (pintype "bidirectional"))
      (node (ref "D36") (pin "2") (pinfunction "CI_2") (pintype "bidirectional"))
    )
    (net (code "74") (name "Net-(D35-DO)") (class "Default")
      (node (ref "D35") (pin "6") (pinfunction "DO_6") (pintype "bidirectional"))
      (node (ref "D36") (pin "1") (pinfunction "DI_1") (pintype "bidirectional"))
    )
    (net (code "75") (name "Net-(D36-CO)") (class "Default")
      (node (ref "D36") (pin "5") (pinfunction "CO_5") (pintype "bidirectional"))
      (node (ref "D37") (pin "2") (pinfunction "CI_2") (pintype "bidirectional"))
    )
    (net (code "76") (name "Net-(D36-DO)") (class "Default")
      (node (ref "D36") (pin "6") (pinfunction "DO_6") (pintype "bidirectional"))
      (node (ref "D37") (pin "1") (pinfunction "DI_1") (pintype "bidirectional"))
    )
    (net (code "77") (name "Net-(D37-CO)") (class "Default")
      (node (ref "D37") (pin "5") (pinfunction "CO_5") (pintype "bidirectional"))
      (node (ref "D38") (pin "2") (pinfunction "CI_2") (pintype "bidirectional"))
    )
    (net (code "78") (name "Net-(D37-DO)") (class "Default")
      (node (ref "D37") (pin "6") (pinfunction "DO_6") (pintype "bidirectional"))
      (node (ref "D38") (pin "1") (pinfunction "DI_1") (pintype "bidirectional"))
    )
    (net (code "79") (name "Net-(D38-CO)") (class "Default")
      (node (ref "D38") (pin "5") (pinfunction "CO_5") (pintype "bidirectional"))
      (node (ref "D39") (pin "2") (pinfunction "CI_2") (pintype "bidirectional"))
    )
    (net (code "80") (name "Net-(D38-DO)") (class "Default")
      (node (ref "D38") (pin "6") (pinfunction "DO_6") (pintype "bidirectional"))
      (node (ref "D39") (pin "1") (pinfunction "DI_1") (pintype "bidirectional"))
    )
    (net (code "81") (name "Net-(D39-CO)") (class "Default")
      (node (ref "D39") (pin "5") (pinfunction "CO_5") (pintype "bidirectional"))
      (node (ref "D40") (pin "2") (pinfunction "CI_2") (pintype "bidirectional"))
    )
    (net (code "82") (name "Net-(D39-DO)") (class "Default")
      (node (ref "D39") (pin "6") (pinfunction "DO_6") (pintype "bidirectional"))
      (node (ref "D40") (pin "1") (pinfunction "DI_1") (pintype "bidirectional"))
    )
    (net (code "83") (name "Net-(D40-CO)") (class "Default")
      (node (ref "D40") (pin "5") (pinfunction "CO_5") (pintype "bidirectional"))
      (node (ref "D41") (pin "2") (pinfunction "CI_2") (pintype "bidirectional"))
    )
    (net (code "84") (name "Net-(D40-DO)") (class "Default")
      (node (ref "D40") (pin "6") (pinfunction "DO_6") (pintype "bidirectional"))
      (node (ref "D41") (pin "1") (pinfunction "DI_1") (pintype "bidirectional"))
    )
    (net (code "85") (name "Net-(D41-CO)") (class "Default")
      (node (ref "D41") (pin "5") (pinfunction "CO_5") (pintype "bidirectional"))
      (node (ref "D42") (pin "2") (pinfunction "CI_2") (pintype "bidirectional"))
    )
    (net (code "86") (name "Net-(D41-DO)") (class "Default")
      (node (ref "D41") (pin "6") (pinfunction "DO_6") (pintype "bidirectional"))
      (node (ref "D42") (pin "1") (pinfunction "DI_1") (pintype "bidirectional"))
    )
    (net (code "87") (name "Net-(D42-CO)") (class "Default")
      (node (ref "D42") (pin "5") (pinfunction "CO_5") (pintype "bidirectional"))
      (node (ref "D43") (pin "2") (pinfunction "CI_2") (pintype "bidirectional"))
    )
    (net (code "88") (name "Net-(D42-DO)") (class "Default")
      (node (ref "D42") (pin "6") (pinfunction "DO_6") (pintype "bidirectional"))
      (node (ref "D43") (pin "1") (pinfunction "DI_1") (pintype "bidirectional"))
    )
    (net (code "89") (name "Net-(D43-CO)") (class "Default")
      (node (ref "D43") (pin "5") (pinfunction "CO_5") (pintype "bidirectional"))
      (node (ref "D44") (pin "2") (pinfunction "CI_2") (pintype "bidirectional"))
    )
    (net (code "90") (name "Net-(D43-DO)") (class "Default")
      (node (ref "D43") (pin "6") (pinfunction "DO_6") (pintype "bidirectional"))
      (node (ref "D44") (pin "1") (pinfunction "DI_1") (pintype "bidirectional"))
    )
    (net (code "91") (name "Net-(D44-CO)") (class "Default")
      (node (ref "D44") (pin "5") (pinfunction "CO_5") (pintype "bidirectional"))
      (node (ref "D45") (pin "2") (pinfunction "CI_2") (pintype "bidirectional"))
    )
    (net (code "92") (name "Net-(D44-DO)") (class "Default")
      (node (ref "D44") (pin "6") (pinfunction "DO_6") (pintype "bidirectional"))
      (node (ref "D45") (pin "1") (pinfunction "DI_1") (pintype "bidirectional"))
    )
    (net (code "93") (name "Net-(D45-CO)") (class "Default")
      (node (ref "D45") (pin "5") (pinfunction "CO_5") (pintype "bidirectional"))
      (node (ref "D46") (pin "2") (pinfunction "CI_2") (pintype "bidirectional"))
    )
    (net (code "94") (name "Net-(D45-DO)") (class "Default")
      (node (ref "D45") (pin "6") (pinfunction "DO_6") (pintype "bidirectional"))
      (node (ref "D46") (pin "1") (pinfunction "DI_1") (pintype "bidirectional"))
    )
    (net (code "95") (name "Net-(D46-CO)") (class "Default")
      (node (ref "D46") (pin "5") (pinfunction "CO_5") (pintype "bidirectional"))
      (node (ref "D47") (pin "2") (pinfunction "CI_2") (pintype "bidirectional"))
    )
    (net (code "96") (name "Net-(D46-DO)") (class "Default")
      (node (ref "D46") (pin "6") (pinfunction "DO_6") (pintype "bidirectional"))
      (node (ref "D47") (pin "1") (pinfunction "DI_1") (pintype "bidirectional"))
    )
    (net (code "97") (name "Net-(D47-CO)") (class "Default")
      (node (ref "D47") (pin "5") (pinfunction "CO_5") (pintype "bidirectional"))
      (node (ref "D48") (pin "2") (pinfunction "CI_2") (pintype "bidirectional"))
    )
    (net (code "98") (name "Net-(D47-DO)") (class "Default")
      (node (ref "D47") (pin "6") (pinfunction "DO_6") (pintype "bidirectional"))
      (node (ref "D48") (pin "1") (pinfunction "DI_1") (pintype "bidirectional"))
    )
    (net (code "99") (name "Net-(D48-CO)") (class "Default")
      (node (ref "D48") (pin "5") (pinfunction "CO_5") (pintype "bidirectional"))
      (node (ref "D49") (pin "2") (pinfunction "CI_2") (pintype "bidirectional"))
    )
    (net (code "100") (name "Net-(D48-DO)") (class "Default")
      (node (ref "D48") (pin "6") (pinfunction "DO_6") (pintype "bidirectional"))
      (node (ref "D49") (pin "1") (pinfunction "DI_1") (pintype "bidirectional"))
    )
    (net (code "101") (name "unconnected-(D49-CO-Pad5)") (class "Default")
      (node (ref "D49") (pin "5") (pinfunction "CO_5") (pintype "bidirectional"))
    )
    (net (code "102") (name "unconnected-(D49-DO-Pad6)") (class "Default")
      (node (ref "D49") (pin "6") (pinfunction "DO_6") (pintype "bidirectional"))
    )
  )
)
